# IO_Receiver.net
KiCad netlist of a schematic drawn in Altium Designer
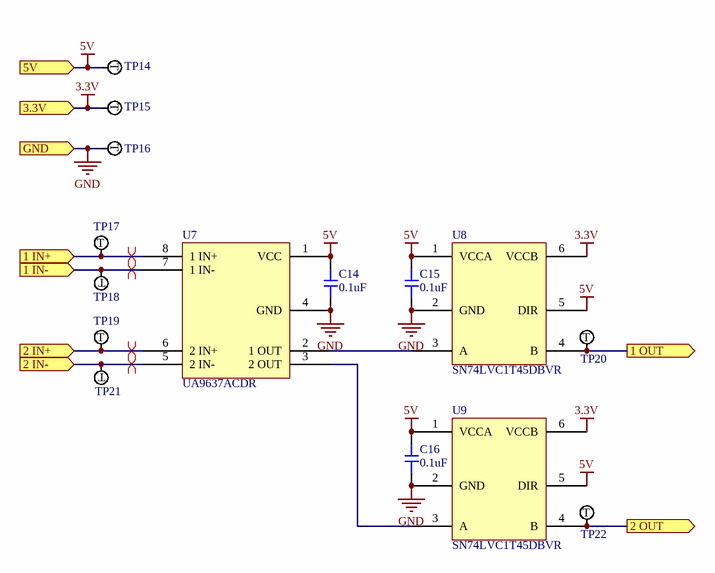
[diagram p0: IO_Receiver.SchDoc]

(export (version "E")
  (design (tool "Eeschema 10.0.6"))
  (components
    (comp (ref "C14")
      (value "0.1uF")
      (footprint "0603-CAP")
      (description "0.1µF ±10% 25V Ceramic Capacitor X7R 0603 (1608 Metric)")
      (fields (field (name "Comment") "CC0603KRX7R8BB104"))
      (libsource (lib "IO_Converter") (part "Capacitor 0.1uF"))
    )
    (comp (ref "C15")
      (value "0.1uF")
      (footprint "0603-CAP")
      (description "0.1µF ±10% 25V Ceramic Capacitor X7R 0603 (1608 Metric)")
      (fields (field (name "Comment") "CC0603KRX7R8BB104"))
      (libsource (lib "IO_Converter") (part "Capacitor 0.1uF"))
    )
    (comp (ref "C16")
      (value "0.1uF")
      (footprint "0603-CAP")
      (description "0.1µF ±10% 25V Ceramic Capacitor X7R 0603 (1608 Metric)")
      (fields (field (name "Comment") "CC0603KRX7R8BB104"))
      (libsource (lib "IO_Converter") (part "Capacitor 0.1uF"))
    )
    (comp (ref "TP14")
      (value "RCU-0C")
      (footprint "RCU-0C")
      (description "PC TEST POINT NATURAL")
      (libsource (lib "IO_Converter") (part "Test Point"))
    )
    (comp (ref "TP15")
      (value "RCU-0C")
      (footprint "RCU-0C")
      (description "PC TEST POINT NATURAL")
      (libsource (lib "IO_Converter") (part "Test Point"))
    )
    (comp (ref "TP16")
      (value "RCU-0C")
      (footprint "RCU-0C")
      (description "PC TEST POINT NATURAL")
      (libsource (lib "IO_Converter") (part "Test Point"))
    )
    (comp (ref "TP17")
      (value "RCU-0C")
      (footprint "RCU-0C")
      (description "PC TEST POINT NATURAL")
      (libsource (lib "IO_Converter") (part "Test Point"))
    )
    (comp (ref "TP18")
      (value "RCU-0C")
      (footprint "RCU-0C")
      (description "PC TEST POINT NATURAL")
      (libsource (lib "IO_Converter") (part "Test Point"))
    )
    (comp (ref "TP19")
      (value "RCU-0C")
      (footprint "RCU-0C")
      (description "PC TEST POINT NATURAL")
      (libsource (lib "IO_Converter") (part "Test Point"))
    )
    (comp (ref "TP20")
      (value "RCU-0C")
      (footprint "RCU-0C")
      (description "PC TEST POINT NATURAL")
      (libsource (lib "IO_Converter") (part "Test Point"))
    )
    (comp (ref "TP21")
      (value "RCU-0C")
      (footprint "RCU-0C")
      (description "PC TEST POINT NATURAL")
      (libsource (lib "IO_Converter") (part "Test Point"))
    )
    (comp (ref "TP22")
      (value "RCU-0C")
      (footprint "RCU-0C")
      (description "PC TEST POINT NATURAL")
      (libsource (lib "IO_Converter") (part "Test Point"))
    )
    (comp (ref "U7")
      (value "UA9637ACDR")
      (footprint "SOIC127P600X175-8N")
      (description "IC RECEIVER 0/2 8SOIC")
      (libsource (lib "IO_Converter") (part "UA9637ACDR"))
    )
    (comp (ref "U8")
      (value "SN74LVC1T45DBVR")
      (footprint "SOT95P280X145-6N")
      (description "IC TRNSLTR BIDIRECTIONAL SOT23-6")
      (libsource (lib "IO_Converter") (part "SN74LVC1T45DBVR"))
    )
    (comp (ref "U9")
      (value "SN74LVC1T45DBVR")
      (footprint "SOT95P280X145-6N")
      (description "IC TRNSLTR BIDIRECTIONAL SOT23-6")
      (libsource (lib "IO_Converter") (part "SN74LVC1T45DBVR"))
    )
  )
  (nets
    (net (code "1") (name "/1 IN+") (class "Default")
      (node (ref "TP17") (pin "1") (pinfunction "1_1") (pintype "passive"))
      (node (ref "U7") (pin "8") (pinfunction "1_IN+_8") (pintype "passive"))
    )
    (net (code "2") (name "/1 IN-") (class "Default")
      (node (ref "TP18") (pin "1") (pinfunction "1_1") (pintype "passive"))
      (node (ref "U7") (pin "7") (pinfunction "1_IN-_7") (pintype "passive"))
    )
    (net (code "3") (name "/1 OUT") (class "Default")
      (node (ref "TP20") (pin "1") (pinfunction "1_1") (pintype "passive"))
      (node (ref "U8") (pin "4") (pinfunction "B_4") (pintype "passive"))
    )
    (net (code "4") (name "/2 IN+") (class "Default")
      (node (ref "TP19") (pin "1") (pinfunction "1_1") (pintype "passive"))
      (node (ref "U7") (pin "6") (pinfunction "2_IN+_6") (pintype "passive"))
    )
    (net (code "5") (name "/2 IN-") (class "Default")
      (node (ref "TP21") (pin "1") (pinfunction "1_1") (pintype "passive"))
      (node (ref "U7") (pin "5") (pinfunction "2_IN-_5") (pintype "passive"))
    )
    (net (code "6") (name "/2 OUT") (class "Default")
      (node (ref "TP22") (pin "1") (pinfunction "1_1") (pintype "passive"))
      (node (ref "U9") (pin "4") (pinfunction "B_4") (pintype "passive"))
    )
    (net (code "7") (name "3.3V") (class "Default")
      (node (ref "TP15") (pin "1") (pinfunction "1_1") (pintype "passive"))
      (node (ref "U8") (pin "6") (pinfunction "VCCB_6") (pintype "passive"))
      (node (ref "U9") (pin "6") (pinfunction "VCCB_6") (pintype "passive"))
    )
    (net (code "8") (name "5V") (class "Default")
      (node (ref "C14") (pin "2") (pinfunction "2_2") (pintype "passive"))
      (node (ref "C15") (pin "2") (pinfunction "2_2") (pintype "passive"))
      (node (ref "C16") (pin "2") (pinfunction "2_2") (pintype "passive"))
      (node (ref "TP14") (pin "1") (pinfunction "1_1") (pintype "passive"))
      (node (ref "U7") (pin "1") (pinfunction "VCC_1") (pintype "passive"))
      (node (ref "U8") (pin "1") (pinfunction "VCCA_1") (pintype "passive"))
      (node (ref "U8") (pin "5") (pinfunction "DIR_5") (pintype "passive"))
      (node (ref "U9") (pin "1") (pinfunction "VCCA_1") (pintype "passive"))
      (node (ref "U9") (pin "5") (pinfunction "DIR_5") (pintype "passive"))
    )
    (net (code "9") (name "GND") (class "Default")
      (node (ref "C14") (pin "1") (pinfunction "1_1") (pintype "passive"))
      (node (ref "C15") (pin "1") (pinfunction "1_1") (pintype "passive"))
      (node (ref "C16") (pin "1") (pinfunction "1_1") (pintype "passive"))
      (node (ref "TP16") (pin "1") (pinfunction "1_1") (pintype "passive"))
      (node (ref "U7") (pin "4") (pinfunction "GND_4") (pintype "passive"))
      (node (ref "U8") (pin "2") (pinfunction "GND_2") (pintype "passive"))
      (node (ref "U9") (pin "2") (pinfunction "GND_2") (pintype "passive"))
    )
    (net (code "10") (name "Net-(U7-1_OUT)") (class "Default")
      (node (ref "U7") (pin "2") (pinfunction "1_OUT_2") (pintype "passive"))
      (node (ref "U8") (pin "3") (pinfunction "A_3") (pintype "passive"))
    )
    (net (code "11") (name "Net-(U7-2_OUT)") (class "Default")
      (node (ref "U7") (pin "3") (pinfunction "2_OUT_3") (pintype "passive"))
      (node (ref "U9") (pin "3") (pinfunction "A_3") (pintype "passive"))
    )
  )
)
